# design.net
KiCad netlist of a schematic drawn in Altium Designer
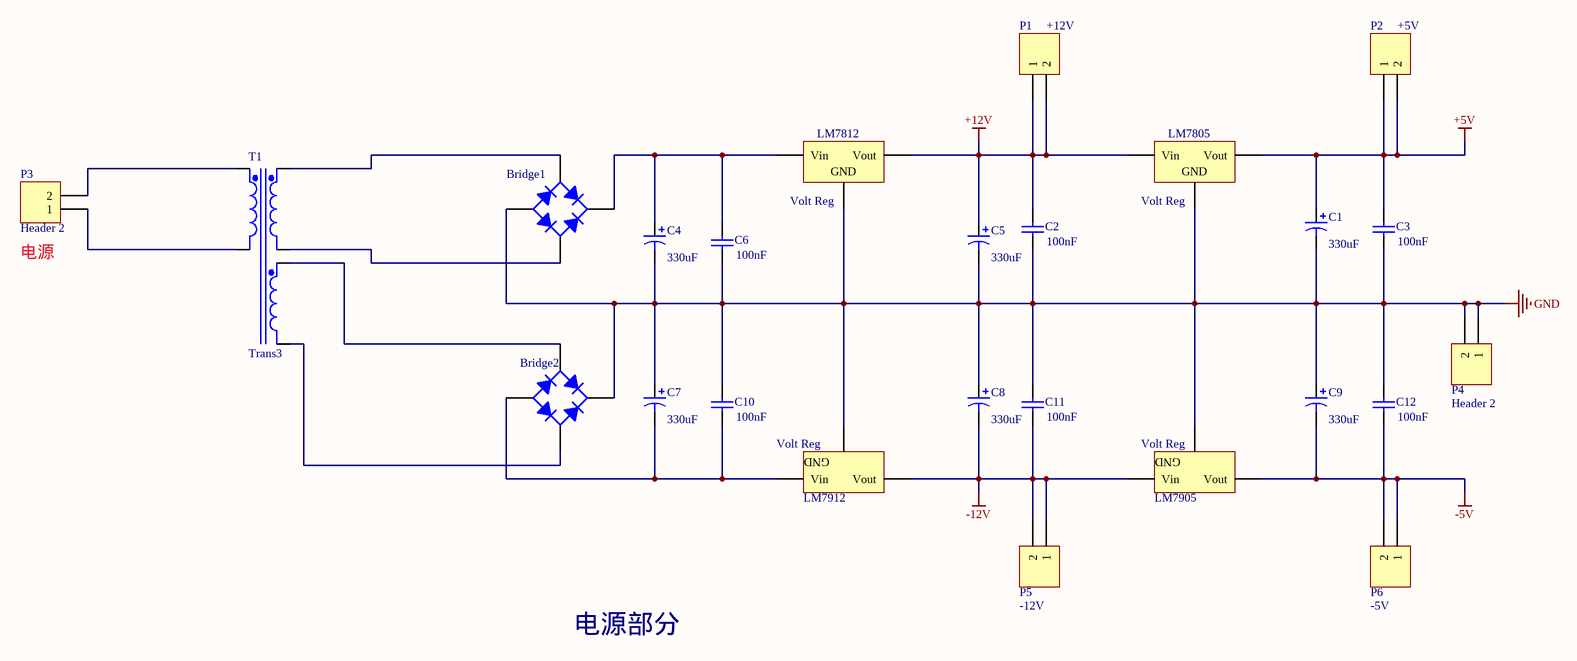
[diagram p0: 稳压电源.SchDoc]

(export (version "E")
  (design (tool "Eeschema 10.0.6"))
  (components
    (comp (ref "C1")
      (value "330uF")
      (footprint "CAPPR2-5x6.8")
      (description "Polarized Capacitor (Radial)")
      (fields (field (name "Comment") "Cap Pol1") (field (name "PUBLISHER") "Altium Limited"))
      (libsource (lib "Miscellaneous Devices") (part "Cap Pol1"))
    )
    (comp (ref "C2")
      (value "100nF")
      (footprint "CAPR2.54-5.1x3.2")
      (description "Capacitor")
      (fields (field (name "Comment") "Cap") (field (name "PUBLISHER") "Altium Limited"))
      (libsource (lib "Miscellaneous Devices") (part "Cap"))
    )
    (comp (ref "C3")
      (value "100nF")
      (footprint "CAPR2.54-5.1x3.2")
      (description "Capacitor")
      (fields (field (name "Comment") "Cap") (field (name "PUBLISHER") "Altium Limited"))
      (libsource (lib "Miscellaneous Devices") (part "Cap"))
    )
    (comp (ref "C4")
      (value "330uF")
      (footprint "CAPPR2-5x6.8")
      (description "Polarized Capacitor (Radial)")
      (fields (field (name "Comment") "Cap Pol1") (field (name "PUBLISHER") "Altium Limited"))
      (libsource (lib "Miscellaneous Devices") (part "Cap Pol1"))
    )
    (comp (ref "C5")
      (value "330uF")
      (footprint "CAPPR2-5x6.8")
      (description "Polarized Capacitor (Radial)")
      (fields (field (name "Comment") "Cap Pol1") (field (name "PUBLISHER") "Altium Limited"))
      (libsource (lib "Miscellaneous Devices") (part "Cap Pol1"))
    )
    (comp (ref "C6")
      (value "100nF")
      (footprint "CAPR2.54-5.1x3.2")
      (description "Capacitor")
      (fields (field (name "Comment") "Cap") (field (name "PUBLISHER") "Altium Limited"))
      (libsource (lib "Miscellaneous Devices") (part "Cap"))
    )
    (comp (ref "C7")
      (value "330uF")
      (footprint "CAPPR2-5x6.8")
      (description "Polarized Capacitor (Radial)")
      (fields (field (name "Comment") "Cap Pol1") (field (name "PUBLISHER") "Altium Limited"))
      (libsource (lib "Miscellaneous Devices") (part "Cap Pol1"))
    )
    (comp (ref "C8")
      (value "330uF")
      (footprint "CAPPR2-5x6.8")
      (description "Polarized Capacitor (Radial)")
      (fields (field (name "Comment") "Cap Pol1") (field (name "PUBLISHER") "Altium Limited"))
      (libsource (lib "Miscellaneous Devices") (part "Cap Pol1"))
    )
    (comp (ref "C9")
      (value "330uF")
      (footprint "CAPPR2-5x6.8")
      (description "Polarized Capacitor (Radial)")
      (fields (field (name "Comment") "Cap Pol1") (field (name "PUBLISHER") "Altium Limited"))
      (libsource (lib "Miscellaneous Devices") (part "Cap Pol1"))
    )
    (comp (ref "C10")
      (value "100nF")
      (footprint "CAPR2.54-5.1x3.2")
      (description "Capacitor")
      (fields (field (name "Comment") "Cap") (field (name "PUBLISHER") "Altium Limited"))
      (libsource (lib "Miscellaneous Devices") (part "Cap"))
    )
    (comp (ref "C11")
      (value "100nF")
      (footprint "CAPR2.54-5.1x3.2")
      (description "Capacitor")
      (fields (field (name "Comment") "Cap") (field (name "PUBLISHER") "Altium Limited"))
      (libsource (lib "Miscellaneous Devices") (part "Cap"))
    )
    (comp (ref "C12")
      (value "100nF")
      (footprint "CAPR2.54-5.1x3.2")
      (description "Capacitor")
      (fields (field (name "Comment") "Cap") (field (name "PUBLISHER") "Altium Limited"))
      (libsource (lib "Miscellaneous Devices") (part "Cap"))
    )
    (comp (ref "D1")
      (value "Bridge1")
      (footprint "整流桥")
      (description "Full Wave Diode Bridge")
      (fields (field (name "PUBLISHER") "Altium Limited"))
      (libsource (lib "Miscellaneous Devices") (part "Bridge1"))
    )
    (comp (ref "D2")
      (value "Bridge2")
      (footprint "整流桥")
      (description "Full Wave Diode Bridge")
      (fields (field (name "PUBLISHER") "Altium Limited"))
      (libsource (lib "Miscellaneous Devices") (part "Bridge1"))
    )
    (comp (ref "LM7805")
      (value "Volt Reg")
      (footprint "TO254P1510-3_4N")
      (description "Voltage Regulator")
      (fields (field (name "PUBLISHER") "Altium Limited"))
      (libsource (lib "") (part "Volt Reg_1"))
    )
    (comp (ref "LM7812")
      (value "Volt Reg")
      (footprint "TO254P1510-3_4N")
      (description "Voltage Regulator")
      (fields (field (name "PUBLISHER") "Altium Limited"))
      (libsource (lib "") (part "Volt Reg_1"))
    )
    (comp (ref "LM7905")
      (value "Volt Reg")
      (footprint "TO254P1510-3_4N")
      (description "Voltage Regulator")
      (fields (field (name "PUBLISHER") "Altium Limited"))
      (libsource (lib "Miscellaneous Devices") (part "Volt Reg"))
    )
    (comp (ref "LM7912")
      (value "Volt Reg")
      (footprint "TO254P1510-3_4N")
      (description "Voltage Regulator")
      (fields (field (name "PUBLISHER") "Altium Limited"))
      (libsource (lib "Miscellaneous Devices") (part "Volt Reg"))
    )
    (comp (ref "P1")
      (value "+12V")
      (footprint "HDR1X2")
      (description "Header, 2-Pin")
      (fields (field (name "PUBLISHER") "Altium Limited"))
      (libsource (lib "Miscellaneous Connectors") (part "Header 2"))
    )
    (comp (ref "P2")
      (value "+5V")
      (footprint "HDR1X2")
      (description "Header, 2-Pin")
      (fields (field (name "PUBLISHER") "Altium Limited"))
      (libsource (lib "Miscellaneous Connectors") (part "Header 2"))
    )
    (comp (ref "P3")
      (value "Header 2")
      (footprint "HDR1X2")
      (description "Header, 2-Pin")
      (fields (field (name "PUBLISHER") "Altium Limited"))
      (libsource (lib "") (part "Header 2_2"))
    )
    (comp (ref "P4")
      (value "Header 2")
      (footprint "HDR1X2")
      (description "Header, 2-Pin")
      (fields (field (name "PUBLISHER") "Altium Limited"))
      (libsource (lib "") (part "Header 2_1"))
    )
    (comp (ref "P5")
      (value "-12V")
      (footprint "HDR1X2")
      (description "Header, 2-Pin")
      (fields (field (name "PUBLISHER") "Altium Limited"))
      (libsource (lib "") (part "Header 2_1"))
    )
    (comp (ref "P6")
      (value "-5V")
      (footprint "HDR1X2")
      (description "Header, 2-Pin")
      (fields (field (name "PUBLISHER") "Altium Limited"))
      (libsource (lib "") (part "Header 2_1"))
    )
    (comp (ref "T1")
      (value "Trans3")
      (footprint "TRF_6")
      (description "Three-winding Transformer (Non-Ideal)")
      (fields (field (name "PUBLISHER") "Altium Limited"))
      (libsource (lib "Miscellaneous Devices") (part "Trans3"))
    )
  )
  (nets
    (net (code "1") (name "+5V") (class "Default")
      (node (ref "C1") (pin "1") (pinfunction "1_1") (pintype "passive"))
      (node (ref "C3") (pin "2") (pinfunction "2_2") (pintype "passive"))
      (node (ref "LM7805") (pin "3") (pinfunction "Vout_3") (pintype "passive"))
      (node (ref "P2") (pin "1") (pinfunction "1_1") (pintype "passive"))
      (node (ref "P2") (pin "2") (pinfunction "2_2") (pintype "passive"))
    )
    (net (code "2") (name "+12V") (class "Default")
      (node (ref "C2") (pin "2") (pinfunction "2_2") (pintype "passive"))
      (node (ref "C5") (pin "1") (pinfunction "1_1") (pintype "passive"))
      (node (ref "LM7805") (pin "1") (pinfunction "Vin_1") (pintype "passive"))
      (node (ref "LM7812") (pin "3") (pinfunction "Vout_3") (pintype "passive"))
      (node (ref "P1") (pin "1") (pinfunction "1_1") (pintype "passive"))
      (node (ref "P1") (pin "2") (pinfunction "2_2") (pintype "passive"))
    )
    (net (code "3") (name "-5V") (class "Default")
      (node (ref "C12") (pin "1") (pinfunction "1_1") (pintype "passive"))
      (node (ref "C9") (pin "2") (pinfunction "2_2") (pintype "passive"))
      (node (ref "LM7905") (pin "3") (pinfunction "Vout_3") (pintype "passive"))
      (node (ref "P6") (pin "1") (pinfunction "1_1") (pintype "passive"))
      (node (ref "P6") (pin "2") (pinfunction "2_2") (pintype "passive"))
    )
    (net (code "4") (name "-12V") (class "Default")
      (node (ref "C11") (pin "1") (pinfunction "1_1") (pintype "passive"))
      (node (ref "C8") (pin "2") (pinfunction "2_2") (pintype "passive"))
      (node (ref "LM7905") (pin "1") (pinfunction "Vin_1") (pintype "passive"))
      (node (ref "LM7912") (pin "3") (pinfunction "Vout_3") (pintype "passive"))
      (node (ref "P5") (pin "1") (pinfunction "1_1") (pintype "passive"))
      (node (ref "P5") (pin "2") (pinfunction "2_2") (pintype "passive"))
    )
    (net (code "5") (name "GND") (class "Default")
      (node (ref "C1") (pin "2") (pinfunction "2_2") (pintype "passive"))
      (node (ref "C10") (pin "2") (pinfunction "2_2") (pintype "passive"))
      (node (ref "C11") (pin "2") (pinfunction "2_2") (pintype "passive"))
      (node (ref "C12") (pin "2") (pinfunction "2_2") (pintype "passive"))
      (node (ref "C2") (pin "1") (pinfunction "1_1") (pintype "passive"))
      (node (ref "C3") (pin "1") (pinfunction "1_1") (pintype "passive"))
      (node (ref "C4") (pin "2") (pinfunction "2_2") (pintype "passive"))
      (node (ref "C5") (pin "2") (pinfunction "2_2") (pintype "passive"))
      (node (ref "C6") (pin "1") (pinfunction "1_1") (pintype "passive"))
      (node (ref "C7") (pin "1") (pinfunction "1_1") (pintype "passive"))
      (node (ref "C8") (pin "1") (pinfunction "1_1") (pintype "passive"))
      (node (ref "C9") (pin "1") (pinfunction "1_1") (pintype "passive"))
      (node (ref "D1") (pin "3") (pinfunction "A_3") (pintype "passive"))
      (node (ref "D2") (pin "1") (pinfunction "K_1") (pintype "passive"))
      (node (ref "LM7805") (pin "2") (pinfunction "GND_2") (pintype "passive"))
      (node (ref "LM7812") (pin "2") (pinfunction "GND_2") (pintype "passive"))
      (node (ref "LM7905") (pin "2") (pinfunction "GND_2") (pintype "passive"))
      (node (ref "LM7912") (pin "2") (pinfunction "GND_2") (pintype "passive"))
      (node (ref "P4") (pin "1") (pinfunction "1_1") (pintype "passive"))
      (node (ref "P4") (pin "2") (pinfunction "2_2") (pintype "passive"))
    )
    (net (code "6") (name "Net-(D1-K)") (class "Default")
      (node (ref "C4") (pin "1") (pinfunction "1_1") (pintype "passive"))
      (node (ref "C6") (pin "2") (pinfunction "2_2") (pintype "passive"))
      (node (ref "D1") (pin "1") (pinfunction "K_1") (pintype "passive"))
      (node (ref "LM7812") (pin "1") (pinfunction "Vin_1") (pintype "passive"))
    )
    (net (code "7") (name "Net-(D2-A)") (class "Default")
      (node (ref "C10") (pin "1") (pinfunction "1_1") (pintype "passive"))
      (node (ref "C7") (pin "2") (pinfunction "2_2") (pintype "passive"))
      (node (ref "D2") (pin "3") (pinfunction "A_3") (pintype "passive"))
      (node (ref "LM7912") (pin "1") (pinfunction "Vin_1") (pintype "passive"))
    )
    (net (code "8") (name "Net-(T1-Pri+)") (class "Default")
      (node (ref "P3") (pin "2") (pinfunction "2_2") (pintype "passive"))
      (node (ref "T1") (pin "1") (pinfunction "Pri+_1") (pintype "passive"))
    )
    (net (code "9") (name "Net-(T1-Pri-)") (class "Default")
      (node (ref "P3") (pin "1") (pinfunction "1_1") (pintype "passive"))
      (node (ref "T1") (pin "2") (pinfunction "Pri-_2") (pintype "passive"))
    )
    (net (code "10") (name "Net-(T1-Sec1+)") (class "Default")
      (node (ref "D1") (pin "4") (pinfunction "C_4") (pintype "passive"))
      (node (ref "T1") (pin "3") (pinfunction "Sec1+_3") (pintype "passive"))
    )
    (net (code "11") (name "Net-(T1-Sec1-)") (class "Default")
      (node (ref "D1") (pin "2") (pinfunction "C_2") (pintype "passive"))
      (node (ref "T1") (pin "4") (pinfunction "Sec1-_4") (pintype "passive"))
    )
    (net (code "12") (name "Net-(T1-Sec2+)") (class "Default")
      (node (ref "D2") (pin "4") (pinfunction "C_4") (pintype "passive"))
      (node (ref "T1") (pin "5") (pinfunction "Sec2+_5") (pintype "passive"))
    )
    (net (code "13") (name "Net-(T1-Sec2-)") (class "Default")
      (node (ref "D2") (pin "2") (pinfunction "C_2") (pintype "passive"))
      (node (ref "T1") (pin "6") (pinfunction "Sec2-_6") (pintype "passive"))
    )
  )
)
